# led-driver.net
KiCad netlist of a schematic drawn in Altium Designer
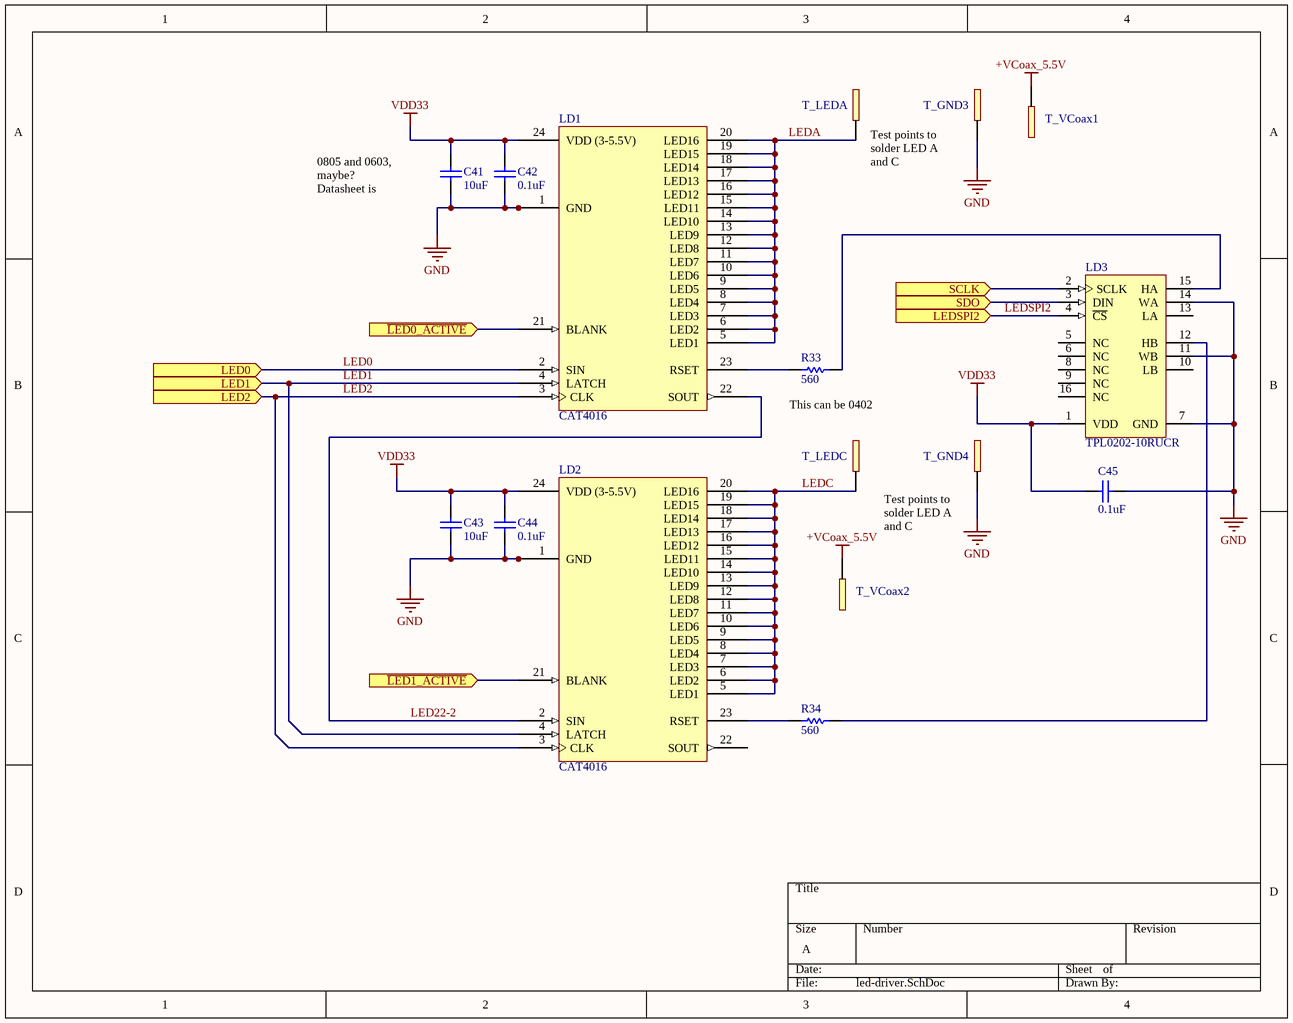
[diagram p0: led-driver.SchDoc]

(export (version "E")
  (design (tool "Eeschema 10.0.6"))
  (components
    (comp (ref "C41")
      (value "10uF")
      (footprint "Cap-0603")
      (description "Capacitor")
      (fields (field (name "Comment") "Cap") (field (name "PUBLISHER") "Altium Limited"))
      (libsource (lib "Miscellaneous Devices") (part "Cap"))
    )
    (comp (ref "C42")
      (value "0.1uF")
      (footprint "Cap_0402")
      (description "Capacitor")
      (fields (field (name "Comment") "Cap") (field (name "PUBLISHER") "Altium Limited"))
      (libsource (lib "Miscellaneous Devices") (part "Cap"))
    )
    (comp (ref "C43")
      (value "10uF")
      (footprint "Cap-0603")
      (description "Capacitor")
      (fields (field (name "Comment") "Cap") (field (name "PUBLISHER") "Altium Limited"))
      (libsource (lib "Miscellaneous Devices") (part "Cap"))
    )
    (comp (ref "C44")
      (value "0.1uF")
      (footprint "Cap_0402")
      (description "Capacitor")
      (fields (field (name "Comment") "Cap") (field (name "PUBLISHER") "Altium Limited"))
      (libsource (lib "Miscellaneous Devices") (part "Cap"))
    )
    (comp (ref "C45")
      (value "0.1uF")
      (footprint "Cap_0402")
      (description "Capacitor")
      (fields (field (name "Comment") "Cap") (field (name "PUBLISHER") "Altium Limited"))
      (libsource (lib "Miscellaneous Devices") (part "Cap"))
    )
    (comp (ref "LD1")
      (value "CAT4016")
      (footprint "TQFN24-4x4mm")
      (description "16-Channel Constant Current LED Driver")
      (libsource (lib "jonnew") (part "CAT4016"))
    )
    (comp (ref "LD2")
      (value "CAT4016")
      (footprint "TQFN24-4x4mm")
      (description "16-Channel Constant Current LED Driver")
      (libsource (lib "jonnew") (part "CAT4016"))
    )
    (comp (ref "LD3")
      (value "TPL0202-10RUCR")
      (footprint "WQFN16-3X3mm")
      (fields (field (name "MANUFACTURER") "Texas Instruments"))
      (libsource (lib "jonnew") (part "TPL0202-10RUCR"))
    )
    (comp (ref "R33")
      (value "560")
      (footprint "Res_0402")
      (description "Resistor")
      (fields (field (name "Comment") "Res1") (field (name "PUBLISHER") "Altium Limited"))
      (libsource (lib "Miscellaneous Devices") (part "Res1"))
    )
    (comp (ref "R34")
      (value "560")
      (footprint "Res_0402")
      (description "Resistor")
      (fields (field (name "Comment") "Res1") (field (name "PUBLISHER") "Altium Limited"))
      (libsource (lib "Miscellaneous Devices") (part "Res1"))
    )
    (comp (ref "T_GND3")
      (value "Header_1PIN")
      (footprint "JUMPER1PIN")
      (libsource (lib "") (part "Header_1PIN_1"))
    )
    (comp (ref "T_GND4")
      (value "Header_1PIN")
      (footprint "JUMPER1PIN")
      (libsource (lib "") (part "Header_1PIN_1"))
    )
    (comp (ref "T_LEDA")
      (value "Header_1PIN")
      (footprint "JUMPER1PIN")
      (libsource (lib "") (part "Header_1PIN_1"))
    )
    (comp (ref "T_LEDC")
      (value "Header_1PIN")
      (footprint "JUMPER1PIN")
      (libsource (lib "") (part "Header_1PIN_1"))
    )
    (comp (ref "T_VCoax1")
      (value "Header_1PIN")
      (footprint "JUMPER1PIN")
      (libsource (lib "Jack_SCH_Lib1") (part "Header_1PIN"))
    )
    (comp (ref "T_VCoax2")
      (value "Header_1PIN")
      (footprint "JUMPER1PIN")
      (libsource (lib "Jack_SCH_Lib1") (part "Header_1PIN"))
    )
  )
  (nets
    (net (code "1") (name "+VCoax_5.5V") (class "Default")
      (node (ref "T_VCoax1") (pin "0") (pinfunction "0_0") (pintype "passive"))
      (node (ref "T_VCoax2") (pin "0") (pinfunction "0_0") (pintype "passive"))
    )
    (net (code "2") (name "/LED0") (class "Default")
      (node (ref "LD1") (pin "2") (pinfunction "SIN_2") (pintype "input"))
    )
    (net (code "3") (name "/LED1") (class "Default")
      (node (ref "LD1") (pin "4") (pinfunction "LATCH_4") (pintype "input"))
      (node (ref "LD2") (pin "4") (pinfunction "LATCH_4") (pintype "input"))
    )
    (net (code "4") (name "/LED2") (class "Default")
      (node (ref "LD1") (pin "3") (pinfunction "CLK_3") (pintype "input"))
      (node (ref "LD2") (pin "3") (pinfunction "CLK_3") (pintype "input"))
    )
    (net (code "5") (name "/LED22-2") (class "Default")
      (node (ref "LD1") (pin "22") (pinfunction "SOUT_22") (pintype "output"))
      (node (ref "LD2") (pin "2") (pinfunction "SIN_2") (pintype "input"))
    )
    (net (code "6") (name "/LEDA") (class "Default")
      (node (ref "LD1") (pin "10") (pinfunction "LED6_10") (pintype "passive"))
      (node (ref "LD1") (pin "11") (pinfunction "LED7_11") (pintype "passive"))
      (node (ref "LD1") (pin "12") (pinfunction "LED8_12") (pintype "passive"))
      (node (ref "LD1") (pin "13") (pinfunction "LED9_13") (pintype "passive"))
      (node (ref "LD1") (pin "14") (pinfunction "LED10_14") (pintype "passive"))
      (node (ref "LD1") (pin "15") (pinfunction "LED11_15") (pintype "passive"))
      (node (ref "LD1") (pin "16") (pinfunction "LED12_16") (pintype "passive"))
      (node (ref "LD1") (pin "17") (pinfunction "LED13_17") (pintype "passive"))
      (node (ref "LD1") (pin "18") (pinfunction "LED14_18") (pintype "passive"))
      (node (ref "LD1") (pin "19") (pinfunction "LED15_19") (pintype "passive"))
      (node (ref "LD1") (pin "20") (pinfunction "LED16_20") (pintype "passive"))
      (node (ref "LD1") (pin "5") (pinfunction "LED1_5") (pintype "passive"))
      (node (ref "LD1") (pin "6") (pinfunction "LED2_6") (pintype "passive"))
      (node (ref "LD1") (pin "7") (pinfunction "LED3_7") (pintype "passive"))
      (node (ref "LD1") (pin "8") (pinfunction "LED4_8") (pintype "passive"))
      (node (ref "LD1") (pin "9") (pinfunction "LED5_9") (pintype "passive"))
      (node (ref "T_LEDA") (pin "0") (pinfunction "0_0") (pintype "passive"))
    )
    (net (code "7") (name "/LEDC") (class "Default")
      (node (ref "LD2") (pin "10") (pinfunction "LED6_10") (pintype "passive"))
      (node (ref "LD2") (pin "11") (pinfunction "LED7_11") (pintype "passive"))
      (node (ref "LD2") (pin "12") (pinfunction "LED8_12") (pintype "passive"))
      (node (ref "LD2") (pin "13") (pinfunction "LED9_13") (pintype "passive"))
      (node (ref "LD2") (pin "14") (pinfunction "LED10_14") (pintype "passive"))
      (node (ref "LD2") (pin "15") (pinfunction "LED11_15") (pintype "passive"))
      (node (ref "LD2") (pin "16") (pinfunction "LED12_16") (pintype "passive"))
      (node (ref "LD2") (pin "17") (pinfunction "LED13_17") (pintype "passive"))
      (node (ref "LD2") (pin "18") (pinfunction "LED14_18") (pintype "passive"))
      (node (ref "LD2") (pin "19") (pinfunction "LED15_19") (pintype "passive"))
      (node (ref "LD2") (pin "20") (pinfunction "LED16_20") (pintype "passive"))
      (node (ref "LD2") (pin "5") (pinfunction "LED1_5") (pintype "passive"))
      (node (ref "LD2") (pin "6") (pinfunction "LED2_6") (pintype "passive"))
      (node (ref "LD2") (pin "7") (pinfunction "LED3_7") (pintype "passive"))
      (node (ref "LD2") (pin "8") (pinfunction "LED4_8") (pintype "passive"))
      (node (ref "LD2") (pin "9") (pinfunction "LED5_9") (pintype "passive"))
      (node (ref "T_LEDC") (pin "0") (pinfunction "0_0") (pintype "passive"))
    )
    (net (code "8") (name "/LEDSPI2") (class "Default")
      (node (ref "LD3") (pin "4") (pinfunction "~{CS}_4") (pintype "input"))
    )
    (net (code "9") (name "/SCLK") (class "Default")
      (node (ref "LD3") (pin "2") (pinfunction "SCLK_2") (pintype "input"))
    )
    (net (code "10") (name "/SDO") (class "Default")
      (node (ref "LD3") (pin "3") (pinfunction "DIN_3") (pintype "input"))
    )
    (net (code "11") (name "/~{LED0_ACTIVE}") (class "Default")
      (node (ref "LD1") (pin "21") (pinfunction "BLANK_21") (pintype "input"))
    )
    (net (code "12") (name "/~{LED1_ACTIVE}") (class "Default")
      (node (ref "LD2") (pin "21") (pinfunction "BLANK_21") (pintype "input"))
    )
    (net (code "13") (name "GND") (class "Default")
      (node (ref "C41") (pin "1") (pinfunction "1_1") (pintype "passive"))
      (node (ref "C42") (pin "1") (pinfunction "1_1") (pintype "passive"))
      (node (ref "C43") (pin "1") (pinfunction "1_1") (pintype "passive"))
      (node (ref "C44") (pin "1") (pinfunction "1_1") (pintype "passive"))
      (node (ref "C45") (pin "2") (pinfunction "2_2") (pintype "passive"))
      (node (ref "LD1") (pin "1") (pinfunction "GND_1") (pintype "power_in"))
      (node (ref "LD1") (pin "PAD") (pintype "power_in"))
      (node (ref "LD2") (pin "1") (pinfunction "GND_1") (pintype "power_in"))
      (node (ref "LD2") (pin "PAD") (pintype "power_in"))
      (node (ref "LD3") (pin "11") (pinfunction "WB_11") (pintype "passive"))
      (node (ref "LD3") (pin "14") (pinfunction "WA_14") (pintype "passive"))
      (node (ref "LD3") (pin "7") (pinfunction "GND_7") (pintype "power_in"))
      (node (ref "T_GND3") (pin "0") (pinfunction "0_0") (pintype "passive"))
      (node (ref "T_GND4") (pin "0") (pinfunction "0_0") (pintype "passive"))
    )
    (net (code "14") (name "Net-(LD1-RSET)") (class "Default")
      (node (ref "LD1") (pin "23") (pinfunction "RSET_23") (pintype "passive"))
      (node (ref "R33") (pin "2") (pinfunction "2_2") (pintype "passive"))
    )
    (net (code "15") (name "Net-(LD2-RSET)") (class "Default")
      (node (ref "LD2") (pin "23") (pinfunction "RSET_23") (pintype "passive"))
      (node (ref "R34") (pin "2") (pinfunction "2_2") (pintype "passive"))
    )
    (net (code "16") (name "Net-(LD3-HA)") (class "Default")
      (node (ref "LD3") (pin "15") (pinfunction "HA_15") (pintype "passive"))
      (node (ref "R33") (pin "1") (pinfunction "1_1") (pintype "passive"))
    )
    (net (code "17") (name "Net-(LD3-HB)") (class "Default")
      (node (ref "LD3") (pin "12") (pinfunction "HB_12") (pintype "passive"))
      (node (ref "R34") (pin "1") (pinfunction "1_1") (pintype "passive"))
    )
    (net (code "18") (name "VDD33") (class "Default")
      (node (ref "C41") (pin "2") (pinfunction "2_2") (pintype "passive"))
      (node (ref "C42") (pin "2") (pinfunction "2_2") (pintype "passive"))
      (node (ref "C43") (pin "2") (pinfunction "2_2") (pintype "passive"))
      (node (ref "C44") (pin "2") (pinfunction "2_2") (pintype "passive"))
      (node (ref "C45") (pin "1") (pinfunction "1_1") (pintype "passive"))
      (node (ref "LD1") (pin "24") (pinfunction "VDD_(3-5.5V)_24") (pintype "power_in"))
      (node (ref "LD2") (pin "24") (pinfunction "VDD_(3-5.5V)_24") (pintype "power_in"))
      (node (ref "LD3") (pin "1") (pinfunction "VDD_1") (pintype "power_in"))
    )
    (net (code "19") (name "unconnected-(LD2-SOUT-Pad22)") (class "Default")
      (node (ref "LD2") (pin "22") (pinfunction "SOUT_22") (pintype "output"))
    )
    (net (code "20") (name "unconnected-(LD3-LA-Pad13)") (class "Default")
      (node (ref "LD3") (pin "13") (pinfunction "LA_13") (pintype "passive"))
    )
    (net (code "21") (name "unconnected-(LD3-LB-Pad10)") (class "Default")
      (node (ref "LD3") (pin "10") (pinfunction "LB_10") (pintype "passive"))
    )
    (net (code "22") (name "unconnected-(LD3-NC-Pad5)") (class "Default")
      (node (ref "LD3") (pin "5") (pinfunction "NC_5") (pintype "passive"))
    )
    (net (code "23") (name "unconnected-(LD3-NC-Pad6)") (class "Default")
      (node (ref "LD3") (pin "6") (pinfunction "NC_6") (pintype "passive"))
    )
    (net (code "24") (name "unconnected-(LD3-NC-Pad8)") (class "Default")
      (node (ref "LD3") (pin "8") (pinfunction "NC_8") (pintype "passive"))
    )
    (net (code "25") (name "unconnected-(LD3-NC-Pad9)") (class "Default")
      (node (ref "LD3") (pin "9") (pinfunction "NC_9") (pintype "passive"))
    )
    (net (code "26") (name "unconnected-(LD3-NC-Pad16)") (class "Default")
      (node (ref "LD3") (pin "16") (pinfunction "NC_16") (pintype "passive"))
    )
  )
)
